# Mother_Board_Bluetooth.net
KiCad netlist of a schematic drawn in Altium Designer
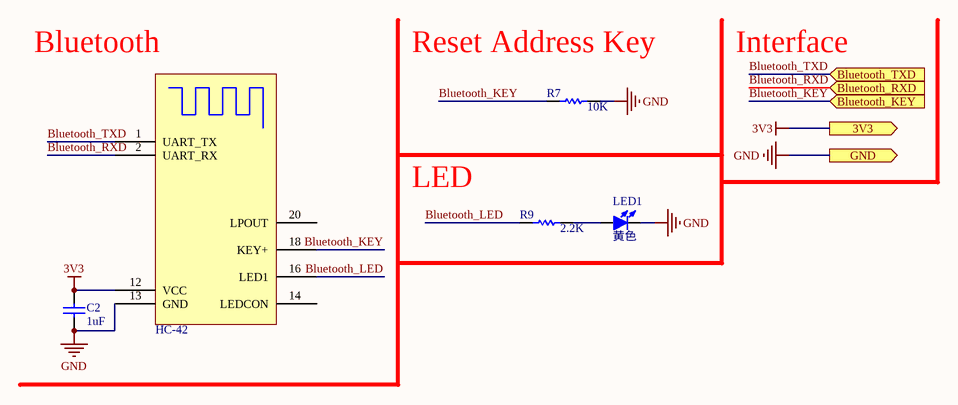
[diagram p0: Mother Board Bluetooth.SchDoc]

(export (version "E")
  (design (tool "Eeschema 10.0.6"))
  (components
    (comp (ref "C2") (value "1uF") (footprint "C0603") (libsource (lib "Cap") (part "Cap")))
    (comp (ref "LED1")
      (value "黄色")
      (footprint "LED 0603Y")
      (description "贴片LED")
      (fields (field (name "版权归属") "源创客"))
      (libsource (lib "All lib") (part "LED-SMD"))
    )
    (comp (ref "R7") (value "10K") (footprint "R0603") (libsource (lib "Res") (part "RES")))
    (comp (ref "R9") (value "2.2K") (footprint "R0603") (libsource (lib "Res") (part "RES")))
    (comp (ref "U2") (value "HC-42") (footprint "HC-42") (libsource (lib "All lib") (part "HC-42")))
  )
  (nets
    (net (code "1") (name "/Bluetooth_KEY") (class "Default")
      (node (ref "R7") (pin "2") (pinfunction "2_2") (pintype "passive"))
      (node (ref "U2") (pin "18") (pinfunction "KEY+_18") (pintype "passive"))
    )
    (net (code "2") (name "/Bluetooth_LED") (class "Default")
      (node (ref "R9") (pin "2") (pinfunction "2_2") (pintype "passive"))
      (node (ref "U2") (pin "16") (pinfunction "LED1_16") (pintype "passive"))
    )
    (net (code "3") (name "/Bluetooth_RXD") (class "Default")
      (node (ref "U2") (pin "2") (pinfunction "UART_RX_2") (pintype "passive"))
    )
    (net (code "4") (name "/Bluetooth_TXD") (class "Default")
      (node (ref "U2") (pin "1") (pinfunction "UART_TX_1") (pintype "passive"))
    )
    (net (code "5") (name "3V3") (class "Default")
      (node (ref "C2") (pin "2") (pinfunction "2_2") (pintype "passive"))
      (node (ref "U2") (pin "12") (pinfunction "VCC_12") (pintype "passive"))
    )
    (net (code "6") (name "GND") (class "Default")
      (node (ref "C2") (pin "1") (pinfunction "1_1") (pintype "passive"))
      (node (ref "LED1") (pin "K") (pinfunction "K_K") (pintype "passive"))
      (node (ref "R7") (pin "1") (pinfunction "1_1") (pintype "passive"))
      (node (ref "U2") (pin "13") (pinfunction "GND_13") (pintype "passive"))
    )
    (net (code "7") (name "Net-(LED1-PadA)") (class "Default")
      (node (ref "LED1") (pin "A") (pinfunction "A_A") (pintype "passive"))
      (node (ref "R9") (pin "1") (pinfunction "1_1") (pintype "passive"))
    )
    (net (code "8") (name "unconnected-(U2-LEDCON-Pad14)") (class "Default")
      (node (ref "U2") (pin "14") (pinfunction "LEDCON_14") (pintype "passive"))
    )
    (net (code "9") (name "unconnected-(U2-LPOUT-Pad20)") (class "Default")
      (node (ref "U2") (pin "20") (pinfunction "LPOUT_20") (pintype "passive"))
    )
  )
)
